# Electromagnetic_Op-Amp_Board.net
KiCad netlist of a schematic drawn in Altium Designer
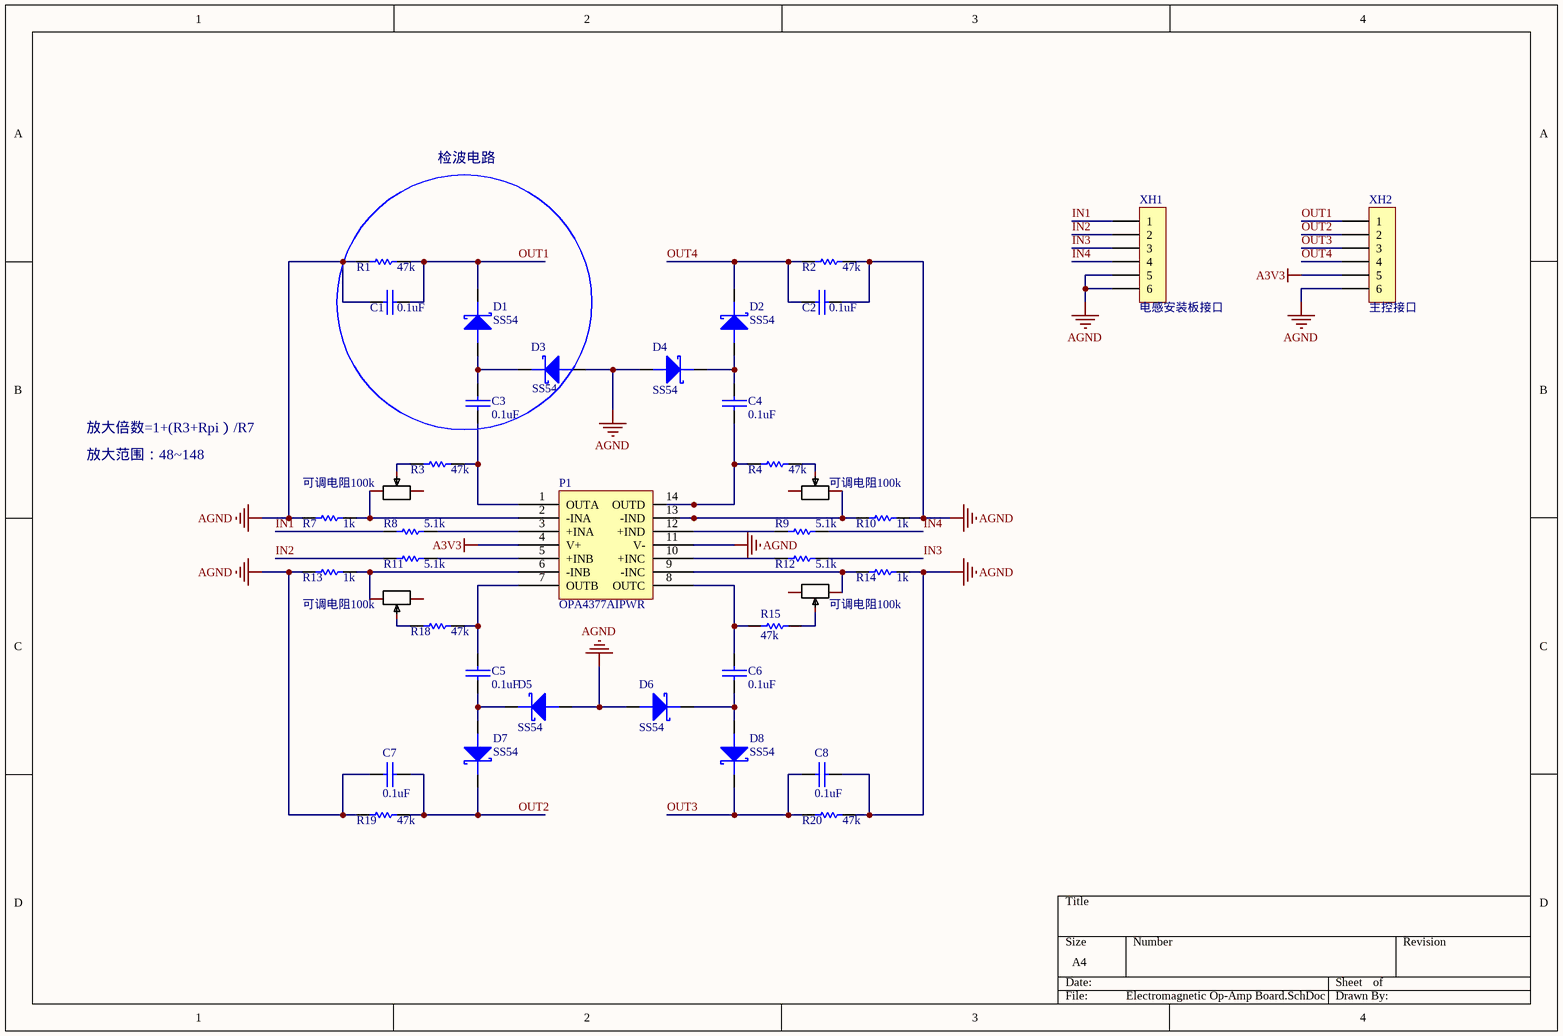
[diagram p0: Electromagnetic Op-Amp Board.SchDoc]

(export (version "E")
  (design (tool "Eeschema 10.0.6"))
  (components
    (comp (ref "C1")
      (value "0.1uF")
      (footprint "0402C")
      (description "无极性电容")
      (libsource (lib "电容") (part "CAP"))
    )
    (comp (ref "C2")
      (value "0.1uF")
      (footprint "0402C")
      (description "无极性电容")
      (libsource (lib "电容") (part "CAP"))
    )
    (comp (ref "C3")
      (value "0.1uF")
      (footprint "0402C")
      (description "无极性电容")
      (libsource (lib "电容") (part "CAP"))
    )
    (comp (ref "C4")
      (value "0.1uF")
      (footprint "0402C")
      (description "无极性电容")
      (libsource (lib "电容") (part "CAP"))
    )
    (comp (ref "C5")
      (value "0.1uF")
      (footprint "0402C")
      (description "无极性电容")
      (libsource (lib "电容") (part "CAP"))
    )
    (comp (ref "C6")
      (value "0.1uF")
      (footprint "0402C")
      (description "无极性电容")
      (libsource (lib "电容") (part "CAP"))
    )
    (comp (ref "C7")
      (value "0.1uF")
      (footprint "0402C")
      (description "无极性电容")
      (libsource (lib "电容") (part "CAP"))
    )
    (comp (ref "C8")
      (value "0.1uF")
      (footprint "0402C")
      (description "无极性电容")
      (libsource (lib "电容") (part "CAP"))
    )
    (comp (ref "D1")
      (value "SS54")
      (footprint "SMA/DO-214AC")
      (description "肖特基二极管")
      (libsource (lib "二极管") (part "DIODE SCHOTTKY"))
    )
    (comp (ref "D2")
      (value "SS54")
      (footprint "SMA/DO-214AC")
      (description "肖特基二极管")
      (libsource (lib "二极管") (part "DIODE SCHOTTKY"))
    )
    (comp (ref "D3")
      (value "SS54")
      (footprint "SMA/DO-214AC")
      (description "肖特基二极管")
      (libsource (lib "二极管") (part "DIODE SCHOTTKY"))
    )
    (comp (ref "D4")
      (value "SS54")
      (footprint "SMA/DO-214AC")
      (description "肖特基二极管")
      (libsource (lib "二极管") (part "DIODE SCHOTTKY"))
    )
    (comp (ref "D5")
      (value "SS54")
      (footprint "SMA/DO-214AC")
      (description "肖特基二极管")
      (libsource (lib "二极管") (part "DIODE SCHOTTKY"))
    )
    (comp (ref "D6")
      (value "SS54")
      (footprint "SMA/DO-214AC")
      (description "肖特基二极管")
      (libsource (lib "二极管") (part "DIODE SCHOTTKY"))
    )
    (comp (ref "D7")
      (value "SS54")
      (footprint "SMA/DO-214AC")
      (description "肖特基二极管")
      (libsource (lib "二极管") (part "DIODE SCHOTTKY"))
    )
    (comp (ref "D8")
      (value "SS54")
      (footprint "SMA/DO-214AC")
      (description "肖特基二极管")
      (libsource (lib "二极管") (part "DIODE SCHOTTKY"))
    )
    (comp (ref "P1")
      (value "OPA4377AIPWR")
      (footprint "OPA4377AIPWR")
      (description "Header, 7-Pin, Dual row")
      (fields (field (name "PUBLISHER") "Altium Limited"))
      (libsource (lib "Schlib1") (part "OPA4377AIPWR"))
    )
    (comp (ref "R1") (value "47k") (footprint "0402R") (libsource (lib "电阻") (part "RES")))
    (comp (ref "R2") (value "47k") (footprint "0402R") (libsource (lib "电阻") (part "RES")))
    (comp (ref "R3") (value "47k") (footprint "0402R") (libsource (lib "电阻") (part "RES")))
    (comp (ref "R4") (value "47k") (footprint "0402R") (libsource (lib "电阻") (part "RES")))
    (comp (ref "R5")
      (value "可调电阻100k")
      (footprint "可调电阻100k")
      (fields
        (field (name "MANUFACTURER") "BOURNS")
        (field (name "MANUFACTURER PART") "3296W-1-104LF")
        (field (name "TOLERANCE") "±10%")
      )
      (libsource (lib "Schlib1") (part "可调电阻100k"))
    )
    (comp (ref "R6")
      (value "可调电阻100k")
      (footprint "可调电阻100k")
      (fields
        (field (name "MANUFACTURER") "BOURNS")
        (field (name "MANUFACTURER PART") "3296W-1-104LF")
        (field (name "TOLERANCE") "±10%")
      )
      (libsource (lib "Schlib1") (part "可调电阻100k"))
    )
    (comp (ref "R7") (value "1k") (footprint "0402R") (libsource (lib "电阻") (part "RES")))
    (comp (ref "R8") (value "5.1k") (footprint "0402R") (libsource (lib "电阻") (part "RES")))
    (comp (ref "R9") (value "5.1k") (footprint "0402R") (libsource (lib "电阻") (part "RES")))
    (comp (ref "R10") (value "1k") (footprint "0402R") (libsource (lib "电阻") (part "RES")))
    (comp (ref "R11") (value "5.1k") (footprint "0402R") (libsource (lib "电阻") (part "RES")))
    (comp (ref "R12") (value "5.1k") (footprint "0402R") (libsource (lib "电阻") (part "RES")))
    (comp (ref "R13") (value "1k") (footprint "0402R") (libsource (lib "电阻") (part "RES")))
    (comp (ref "R14") (value "1k") (footprint "0402R") (libsource (lib "电阻") (part "RES")))
    (comp (ref "R15") (value "47k") (footprint "0402R") (libsource (lib "电阻") (part "RES")))
    (comp (ref "R16")
      (value "可调电阻100k")
      (footprint "可调电阻100k")
      (fields
        (field (name "MANUFACTURER") "BOURNS")
        (field (name "MANUFACTURER PART") "3296W-1-104LF")
        (field (name "TOLERANCE") "±10%")
      )
      (libsource (lib "Schlib1") (part "可调电阻100k"))
    )
    (comp (ref "R17")
      (value "可调电阻100k")
      (footprint "可调电阻100k")
      (fields
        (field (name "MANUFACTURER") "BOURNS")
        (field (name "MANUFACTURER PART") "3296W-1-104LF")
        (field (name "TOLERANCE") "±10%")
      )
      (libsource (lib "Schlib1") (part "可调电阻100k"))
    )
    (comp (ref "R18") (value "47k") (footprint "0402R") (libsource (lib "电阻") (part "RES")))
    (comp (ref "R19") (value "47k") (footprint "0402R") (libsource (lib "电阻") (part "RES")))
    (comp (ref "R20") (value "47k") (footprint "0402R") (libsource (lib "电阻") (part "RES")))
    (comp (ref "XH1") (value "电感安装板接口") (footprint "XH6/2.54mm/180") (libsource (lib "XH，VH") (part "XH6")))
    (comp (ref "XH2") (value "主控接口") (footprint "XH6/2.54mm/180") (libsource (lib "XH，VH") (part "XH6")))
  )
  (nets
    (net (code "1") (name "/IN1") (class "Default")
      (node (ref "R8") (pin "1") (pinfunction "1_1") (pintype "passive"))
      (node (ref "XH1") (pin "1") (pinfunction "1_1") (pintype "passive"))
    )
    (net (code "2") (name "/IN2") (class "Default")
      (node (ref "R11") (pin "1") (pinfunction "1_1") (pintype "passive"))
      (node (ref "XH1") (pin "2") (pinfunction "2_2") (pintype "passive"))
    )
    (net (code "3") (name "/IN3") (class "Default")
      (node (ref "R12") (pin "2") (pinfunction "2_2") (pintype "passive"))
      (node (ref "XH1") (pin "3") (pinfunction "3_3") (pintype "passive"))
    )
    (net (code "4") (name "/IN4") (class "Default")
      (node (ref "R9") (pin "2") (pinfunction "2_2") (pintype "passive"))
      (node (ref "XH1") (pin "4") (pinfunction "4_4") (pintype "passive"))
    )
    (net (code "5") (name "/OUT1") (class "Default")
      (node (ref "C1") (pin "1") (pinfunction "1_1") (pintype "passive"))
      (node (ref "D1") (pin "K") (pinfunction "K_K") (pintype "passive"))
      (node (ref "R1") (pin "2") (pinfunction "2_2") (pintype "passive"))
      (node (ref "XH2") (pin "1") (pinfunction "1_1") (pintype "passive"))
    )
    (net (code "6") (name "/OUT2") (class "Default")
      (node (ref "C7") (pin "1") (pinfunction "1_1") (pintype "passive"))
      (node (ref "D7") (pin "K") (pinfunction "K_K") (pintype "passive"))
      (node (ref "R19") (pin "2") (pinfunction "2_2") (pintype "passive"))
      (node (ref "XH2") (pin "2") (pinfunction "2_2") (pintype "passive"))
    )
    (net (code "7") (name "/OUT3") (class "Default")
      (node (ref "C8") (pin "2") (pinfunction "2_2") (pintype "passive"))
      (node (ref "D8") (pin "K") (pinfunction "K_K") (pintype "passive"))
      (node (ref "R20") (pin "1") (pinfunction "1_1") (pintype "passive"))
      (node (ref "XH2") (pin "3") (pinfunction "3_3") (pintype "passive"))
    )
    (net (code "8") (name "/OUT4") (class "Default")
      (node (ref "C2") (pin "2") (pinfunction "2_2") (pintype "passive"))
      (node (ref "D2") (pin "K") (pinfunction "K_K") (pintype "passive"))
      (node (ref "R2") (pin "1") (pinfunction "1_1") (pintype "passive"))
      (node (ref "XH2") (pin "4") (pinfunction "4_4") (pintype "passive"))
    )
    (net (code "9") (name "A3V3") (class "Default")
      (node (ref "P1") (pin "4") (pinfunction "V+_4") (pintype "passive"))
      (node (ref "XH2") (pin "5") (pinfunction "5_5") (pintype "passive"))
    )
    (net (code "10") (name "AGND") (class "Default")
      (node (ref "C1") (pin "2") (pinfunction "2_2") (pintype "passive"))
      (node (ref "C2") (pin "1") (pinfunction "1_1") (pintype "passive"))
      (node (ref "C7") (pin "2") (pinfunction "2_2") (pintype "passive"))
      (node (ref "C8") (pin "1") (pinfunction "1_1") (pintype "passive"))
      (node (ref "D3") (pin "A") (pinfunction "A_A") (pintype "passive"))
      (node (ref "D4") (pin "A") (pinfunction "A_A") (pintype "passive"))
      (node (ref "D5") (pin "A") (pinfunction "A_A") (pintype "passive"))
      (node (ref "D6") (pin "A") (pinfunction "A_A") (pintype "passive"))
      (node (ref "P1") (pin "11") (pinfunction "V-_11") (pintype "passive"))
      (node (ref "R1") (pin "1") (pinfunction "1_1") (pintype "passive"))
      (node (ref "R10") (pin "2") (pinfunction "2_2") (pintype "passive"))
      (node (ref "R13") (pin "1") (pinfunction "1_1") (pintype "passive"))
      (node (ref "R14") (pin "2") (pinfunction "2_2") (pintype "passive"))
      (node (ref "R19") (pin "1") (pinfunction "1_1") (pintype "passive"))
      (node (ref "R2") (pin "2") (pinfunction "2_2") (pintype "passive"))
      (node (ref "R20") (pin "2") (pinfunction "2_2") (pintype "passive"))
      (node (ref "R7") (pin "1") (pinfunction "1_1") (pintype "passive"))
      (node (ref "XH1") (pin "5") (pinfunction "5_5") (pintype "passive"))
      (node (ref "XH1") (pin "6") (pinfunction "6_6") (pintype "passive"))
      (node (ref "XH2") (pin "6") (pinfunction "6_6") (pintype "passive"))
    )
    (net (code "11") (name "Net-(C3-Pad2)") (class "Default")
      (node (ref "C3") (pin "2") (pinfunction "2_2") (pintype "passive"))
      (node (ref "D1") (pin "A") (pinfunction "A_A") (pintype "passive"))
      (node (ref "D3") (pin "K") (pinfunction "K_K") (pintype "passive"))
    )
    (net (code "12") (name "Net-(C4-Pad2)") (class "Default")
      (node (ref "C4") (pin "2") (pinfunction "2_2") (pintype "passive"))
      (node (ref "D2") (pin "A") (pinfunction "A_A") (pintype "passive"))
      (node (ref "D4") (pin "K") (pinfunction "K_K") (pintype "passive"))
    )
    (net (code "13") (name "Net-(C5-Pad2)") (class "Default")
      (node (ref "C5") (pin "2") (pinfunction "2_2") (pintype "passive"))
      (node (ref "D5") (pin "K") (pinfunction "K_K") (pintype "passive"))
      (node (ref "D7") (pin "A") (pinfunction "A_A") (pintype "passive"))
    )
    (net (code "14") (name "Net-(C6-Pad2)") (class "Default")
      (node (ref "C6") (pin "2") (pinfunction "2_2") (pintype "passive"))
      (node (ref "D6") (pin "K") (pinfunction "K_K") (pintype "passive"))
      (node (ref "D8") (pin "A") (pinfunction "A_A") (pintype "passive"))
    )
    (net (code "15") (name "Net-(P1-+INA)") (class "Default")
      (node (ref "P1") (pin "3") (pinfunction "+INA_3") (pintype "passive"))
      (node (ref "R8") (pin "2") (pinfunction "2_2") (pintype "passive"))
    )
    (net (code "16") (name "Net-(P1-+INB)") (class "Default")
      (node (ref "P1") (pin "5") (pinfunction "+INB_5") (pintype "passive"))
      (node (ref "R11") (pin "2") (pinfunction "2_2") (pintype "passive"))
    )
    (net (code "17") (name "Net-(P1-+INC)") (class "Default")
      (node (ref "P1") (pin "10") (pinfunction "+INC_10") (pintype "passive"))
      (node (ref "R12") (pin "1") (pinfunction "1_1") (pintype "passive"))
    )
    (net (code "18") (name "Net-(P1-+IND)") (class "Default")
      (node (ref "P1") (pin "12") (pinfunction "+IND_12") (pintype "passive"))
      (node (ref "R9") (pin "1") (pinfunction "1_1") (pintype "passive"))
    )
    (net (code "19") (name "Net-(P1--INA)") (class "Default")
      (node (ref "P1") (pin "2") (pinfunction "-INA_2") (pintype "passive"))
      (node (ref "R5") (pin "3") (pinfunction "3_3") (pintype "passive"))
      (node (ref "R7") (pin "2") (pinfunction "2_2") (pintype "passive"))
    )
    (net (code "20") (name "Net-(P1--INB)") (class "Default")
      (node (ref "P1") (pin "6") (pinfunction "-INB_6") (pintype "passive"))
      (node (ref "R13") (pin "2") (pinfunction "2_2") (pintype "passive"))
      (node (ref "R17") (pin "1") (pinfunction "1_1") (pintype "passive"))
    )
    (net (code "21") (name "Net-(P1--INC)") (class "Default")
      (node (ref "P1") (pin "9") (pinfunction "-INC_9") (pintype "passive"))
      (node (ref "R14") (pin "1") (pinfunction "1_1") (pintype "passive"))
      (node (ref "R16") (pin "3") (pinfunction "3_3") (pintype "passive"))
    )
    (net (code "22") (name "Net-(P1--IND)") (class "Default")
      (node (ref "P1") (pin "13") (pinfunction "-IND_13") (pintype "passive"))
      (node (ref "R10") (pin "1") (pinfunction "1_1") (pintype "passive"))
      (node (ref "R6") (pin "1") (pinfunction "1_1") (pintype "passive"))
    )
    (net (code "23") (name "Net-(P1-OUTA)") (class "Default")
      (node (ref "C3") (pin "1") (pinfunction "1_1") (pintype "passive"))
      (node (ref "P1") (pin "1") (pinfunction "OUTA_1") (pintype "passive"))
      (node (ref "R3") (pin "2") (pinfunction "2_2") (pintype "passive"))
    )
    (net (code "24") (name "Net-(P1-OUTB)") (class "Default")
      (node (ref "C5") (pin "1") (pinfunction "1_1") (pintype "passive"))
      (node (ref "P1") (pin "7") (pinfunction "OUTB_7") (pintype "passive"))
      (node (ref "R18") (pin "2") (pinfunction "2_2") (pintype "passive"))
    )
    (net (code "25") (name "Net-(P1-OUTC)") (class "Default")
      (node (ref "C6") (pin "1") (pinfunction "1_1") (pintype "passive"))
      (node (ref "P1") (pin "8") (pinfunction "OUTC_8") (pintype "passive"))
      (node (ref "R15") (pin "1") (pinfunction "1_1") (pintype "passive"))
    )
    (net (code "26") (name "Net-(P1-OUTD)") (class "Default")
      (node (ref "C4") (pin "1") (pinfunction "1_1") (pintype "passive"))
      (node (ref "P1") (pin "14") (pinfunction "OUTD_14") (pintype "passive"))
      (node (ref "R4") (pin "1") (pinfunction "1_1") (pintype "passive"))
    )
    (net (code "27") (name "Net-(R3-Pad1)") (class "Default")
      (node (ref "R3") (pin "1") (pinfunction "1_1") (pintype "passive"))
      (node (ref "R5") (pin "2") (pinfunction "2_2") (pintype "passive"))
    )
    (net (code "28") (name "Net-(R4-Pad2)") (class "Default")
      (node (ref "R4") (pin "2") (pinfunction "2_2") (pintype "passive"))
      (node (ref "R6") (pin "2") (pinfunction "2_2") (pintype "passive"))
    )
    (net (code "29") (name "Net-(R15-Pad2)") (class "Default")
      (node (ref "R15") (pin "2") (pinfunction "2_2") (pintype "passive"))
      (node (ref "R16") (pin "2") (pinfunction "2_2") (pintype "passive"))
    )
    (net (code "30") (name "Net-(R17-Pad2)") (class "Default")
      (node (ref "R17") (pin "2") (pinfunction "2_2") (pintype "passive"))
      (node (ref "R18") (pin "1") (pinfunction "1_1") (pintype "passive"))
    )
    (net (code "31") (name "unconnected-(R5-Pad1)") (class "Default")
      (node (ref "R5") (pin "1") (pinfunction "1_1") (pintype "passive"))
    )
    (net (code "32") (name "unconnected-(R6-Pad3)") (class "Default")
      (node (ref "R6") (pin "3") (pinfunction "3_3") (pintype "passive"))
    )
    (net (code "33") (name "unconnected-(R16-Pad1)") (class "Default")
      (node (ref "R16") (pin "1") (pinfunction "1_1") (pintype "passive"))
    )
    (net (code "34") (name "unconnected-(R17-Pad3)") (class "Default")
      (node (ref "R17") (pin "3") (pinfunction "3_3") (pintype "passive"))
    )
  )
)
